# PD_Controller.net
KiCad netlist of a schematic drawn in Altium Designer
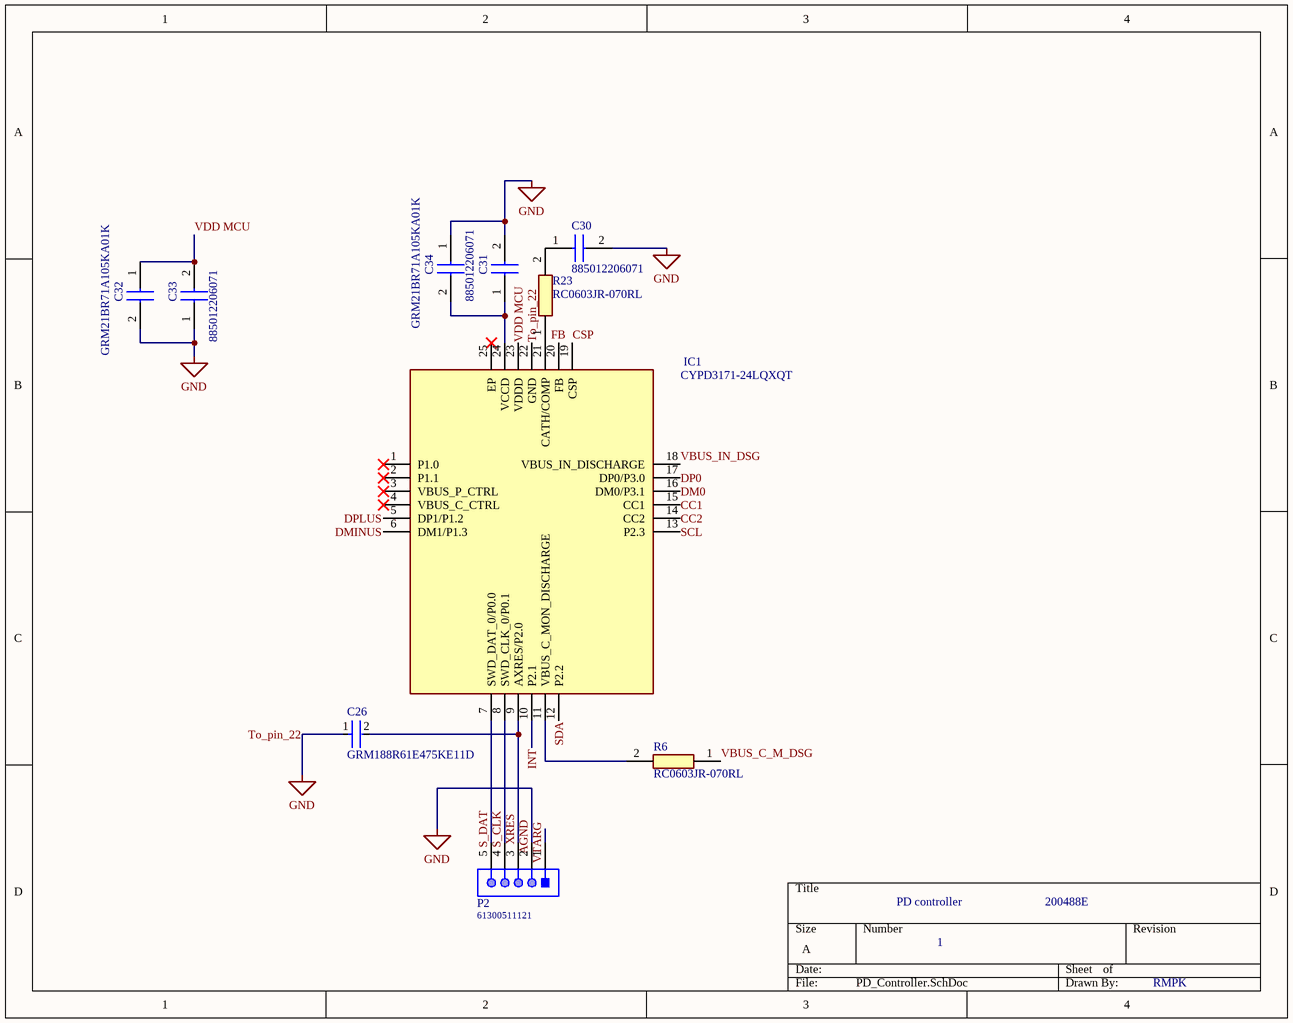
[diagram p0: PD_Controller.SchDoc]

(export (version "E")
  (design (tool "Eeschema 10.0.6"))
  (components
    (comp (ref "C26")
      (value "GRM188R61E475KE11D")
      (footprint "FP-GRM188-0_15-IPC_C")
      (description "Chip Multilayer Ceramic Capacitors for General Purpose, 0603, 4.7uF, X5R, 15%, 10%, 25V")
      (fields (field (name "VOLTAGE") "25V") (field (name "TOLERANCE") "10%"))
      (libsource (lib "Altium Content Vault") (part "02cd4be3c70576c341d710602a673aa"))
    )
    (comp (ref "C30")
      (value "885012206071")
      (footprint "SamacSys:CAPC1608X87N")
      (description "Capacitor")
      (fields (field (name "MOUSER PART NUMBER") "710-885012206071"))
      (libsource (lib "*") (part "885012206071"))
    )
    (comp (ref "C31")
      (value "885012206071")
      (footprint "SamacSys:CAPC1608X87N")
      (description "Capacitor")
      (fields (field (name "MOUSER PART NUMBER") "710-885012206071"))
      (libsource (lib "*") (part "885012206071"))
    )
    (comp (ref "C32")
      (value "GRM21BR71A105KA01K")
      (footprint "SamacSys:CAPC2012X145N")
      (description "Capacitor")
      (fields (field (name "MOUSER PART NUMBER") "81-GRM40X105K10K"))
      (libsource (lib "*") (part "GRM21BR71A105KA01K"))
    )
    (comp (ref "C33")
      (value "885012206071")
      (footprint "SamacSys:CAPC1608X87N")
      (description "Capacitor")
      (fields (field (name "MOUSER PART NUMBER") "710-885012206071"))
      (libsource (lib "*") (part "885012206071"))
    )
    (comp (ref "C34")
      (value "GRM21BR71A105KA01K")
      (footprint "SamacSys:CAPC2012X145N")
      (description "Capacitor")
      (fields (field (name "MOUSER PART NUMBER") "81-GRM40X105K10K"))
      (libsource (lib "*") (part "GRM21BR71A105KA01K"))
    )
    (comp (ref "IC1")
      (value "CYPD3171-24LQXQT")
      (footprint "SamacSys:QFN50P400X400X60-25N-D")
      (description "Integrated Circuit")
      (fields (field (name "MOUSER PART NUMBER") "727-CYPD3171-24LQXQT"))
      (libsource (lib "*") (part "CYPD3171-24LQXQT"))
    )
    (comp (ref "P2")
      (value "61300511121")
      (footprint "61300511121")
      (description "THT Vertical Pin Header WR-PHD, Pitch 2.54 mm, Single Row, 5 pins")
      (fields (field (name "MANUFACTURER") "Wurth Elektronik") (field (name "PUBLISHER") "WurthElektronik"))
      (libsource (lib "Altium Content Vault") (part "WE-CN-1P-M-R5"))
    )
    (comp (ref "R6")
      (value "RC0603JR-070RL")
      (footprint "SamacSys:RESC1608X55N")
      (description "Resistor")
      (fields (field (name "MOUSER PART NUMBER") "603-RC0603JR-070RL"))
      (libsource (lib "*") (part "RC0603JR-070RL"))
    )
    (comp (ref "R23")
      (value "RC0603JR-070RL")
      (footprint "SamacSys:RESC1608X55N")
      (description "Resistor")
      (fields (field (name "MOUSER PART NUMBER") "603-RC0603JR-070RL"))
      (libsource (lib "") (part "RC0603JR-070RL_1"))
    )
  )
  (nets
    (net (code "1") (name "/CC1") (class "Default")
      (node (ref "IC1") (pin "15") (pinfunction "CC1_15") (pintype "passive"))
    )
    (net (code "2") (name "/CC2") (class "Default")
      (node (ref "IC1") (pin "14") (pinfunction "CC2_14") (pintype "passive"))
    )
    (net (code "3") (name "/CSP") (class "Default")
      (node (ref "IC1") (pin "19") (pinfunction "CSP_19") (pintype "passive"))
    )
    (net (code "4") (name "/DM0") (class "Default")
      (node (ref "IC1") (pin "16") (pinfunction "DM0/P3.1_16") (pintype "passive"))
    )
    (net (code "5") (name "/DMINUS") (class "Default")
      (node (ref "IC1") (pin "6") (pinfunction "DM1/P1.3_6") (pintype "passive"))
    )
    (net (code "6") (name "/DP0") (class "Default")
      (node (ref "IC1") (pin "17") (pinfunction "DP0/P3.0_17") (pintype "passive"))
    )
    (net (code "7") (name "/DPLUS") (class "Default")
      (node (ref "IC1") (pin "5") (pinfunction "DP1/P1.2_5") (pintype "passive"))
    )
    (net (code "8") (name "/FB") (class "Default")
      (node (ref "IC1") (pin "20") (pinfunction "FB_20") (pintype "passive"))
    )
    (net (code "9") (name "/INT") (class "Default")
      (node (ref "IC1") (pin "10") (pinfunction "P2.1_10") (pintype "passive"))
    )
    (net (code "10") (name "/SCL") (class "Default")
      (node (ref "IC1") (pin "13") (pinfunction "P2.3_13") (pintype "passive"))
    )
    (net (code "11") (name "/SDA") (class "Default")
      (node (ref "IC1") (pin "12") (pinfunction "P2.2_12") (pintype "passive"))
    )
    (net (code "12") (name "/S_CLK") (class "Default")
      (node (ref "IC1") (pin "8") (pinfunction "SWD_CLK_0/P0.1_8") (pintype "passive"))
      (node (ref "P2") (pin "4") (pinfunction "4_4") (pintype "passive"))
    )
    (net (code "13") (name "/S_DAT") (class "Default")
      (node (ref "IC1") (pin "7") (pinfunction "SWD_DAT_0/P0.0_7") (pintype "passive"))
      (node (ref "P2") (pin "5") (pinfunction "5_5") (pintype "passive"))
    )
    (net (code "14") (name "/VBUS_C_M_DSG") (class "Default")
      (node (ref "R6") (pin "1") (pinfunction "1_1") (pintype "passive"))
    )
    (net (code "15") (name "/VBUS_IN_DSG") (class "Default")
      (node (ref "IC1") (pin "18") (pinfunction "VBUS_IN_DISCHARGE_18") (pintype "passive"))
    )
    (net (code "16") (name "/VDD MCU") (class "Default")
      (node (ref "C32") (pin "1") (pinfunction "1_1") (pintype "passive"))
      (node (ref "C33") (pin "2") (pinfunction "2_2") (pintype "passive"))
      (node (ref "IC1") (pin "23") (pinfunction "VDDD_23") (pintype "passive"))
    )
    (net (code "17") (name "/VTARG") (class "Default")
      (node (ref "P2") (pin "1") (pinfunction "1_1") (pintype "passive"))
    )
    (net (code "18") (name "/XRES") (class "Default")
      (node (ref "C26") (pin "2") (pinfunction "2_2") (pintype "passive"))
      (node (ref "IC1") (pin "9") (pinfunction "AXRES/P2.0_9") (pintype "passive"))
      (node (ref "P2") (pin "3") (pinfunction "3_3") (pintype "passive"))
    )
    (net (code "19") (name "GND") (class "Default")
      (node (ref "C26") (pin "1") (pinfunction "1_1") (pintype "passive"))
      (node (ref "C30") (pin "2") (pinfunction "2_2") (pintype "passive"))
      (node (ref "C31") (pin "2") (pinfunction "2_2") (pintype "passive"))
      (node (ref "C32") (pin "2") (pinfunction "2_2") (pintype "passive"))
      (node (ref "C33") (pin "1") (pinfunction "1_1") (pintype "passive"))
      (node (ref "C34") (pin "1") (pinfunction "1_1") (pintype "passive"))
      (node (ref "IC1") (pin "22") (pinfunction "GND_22") (pintype "passive"))
      (node (ref "P2") (pin "2") (pinfunction "2_2") (pintype "passive"))
    )
    (net (code "20") (name "Net-(C30-Pad1)") (class "Default")
      (node (ref "C30") (pin "1") (pinfunction "1_1") (pintype "passive"))
      (node (ref "R23") (pin "2") (pinfunction "2_2") (pintype "passive"))
    )
    (net (code "21") (name "Net-(IC1-CATH{slash}COMP)") (class "Default")
      (node (ref "IC1") (pin "21") (pinfunction "CATH/COMP_21") (pintype "passive"))
      (node (ref "R23") (pin "1") (pinfunction "1_1") (pintype "passive"))
    )
    (net (code "22") (name "Net-(IC1-VBUS_C_MON_DISCHARGE)") (class "Default")
      (node (ref "IC1") (pin "11") (pinfunction "VBUS_C_MON_DISCHARGE_11") (pintype "passive"))
      (node (ref "R6") (pin "2") (pinfunction "2_2") (pintype "passive"))
    )
    (net (code "23") (name "Net-(IC1-VCCD)") (class "Default")
      (node (ref "C31") (pin "1") (pinfunction "1_1") (pintype "passive"))
      (node (ref "C34") (pin "2") (pinfunction "2_2") (pintype "passive"))
      (node (ref "IC1") (pin "24") (pinfunction "VCCD_24") (pintype "passive"))
    )
    (net (code "24") (name "unconnected-(IC1-EP-Pad25)") (class "Default")
      (node (ref "IC1") (pin "25") (pinfunction "EP_25") (pintype "passive+no_connect"))
    )
    (net (code "25") (name "unconnected-(IC1-P1.0-Pad1)") (class "Default")
      (node (ref "IC1") (pin "1") (pinfunction "P1.0_1") (pintype "passive+no_connect"))
    )
    (net (code "26") (name "unconnected-(IC1-P1.1-Pad2)") (class "Default")
      (node (ref "IC1") (pin "2") (pinfunction "P1.1_2") (pintype "passive+no_connect"))
    )
    (net (code "27") (name "unconnected-(IC1-VBUS_C_CTRL-Pad4)") (class "Default")
      (node (ref "IC1") (pin "4") (pinfunction "VBUS_C_CTRL_4") (pintype "passive+no_connect"))
    )
    (net (code "28") (name "unconnected-(IC1-VBUS_P_CTRL-Pad3)") (class "Default")
      (node (ref "IC1") (pin "3") (pinfunction "VBUS_P_CTRL_3") (pintype "passive+no_connect"))
    )
  )
)
